# Rocketometer2148.net
KiCad netlist of a schematic drawn in EAGLE
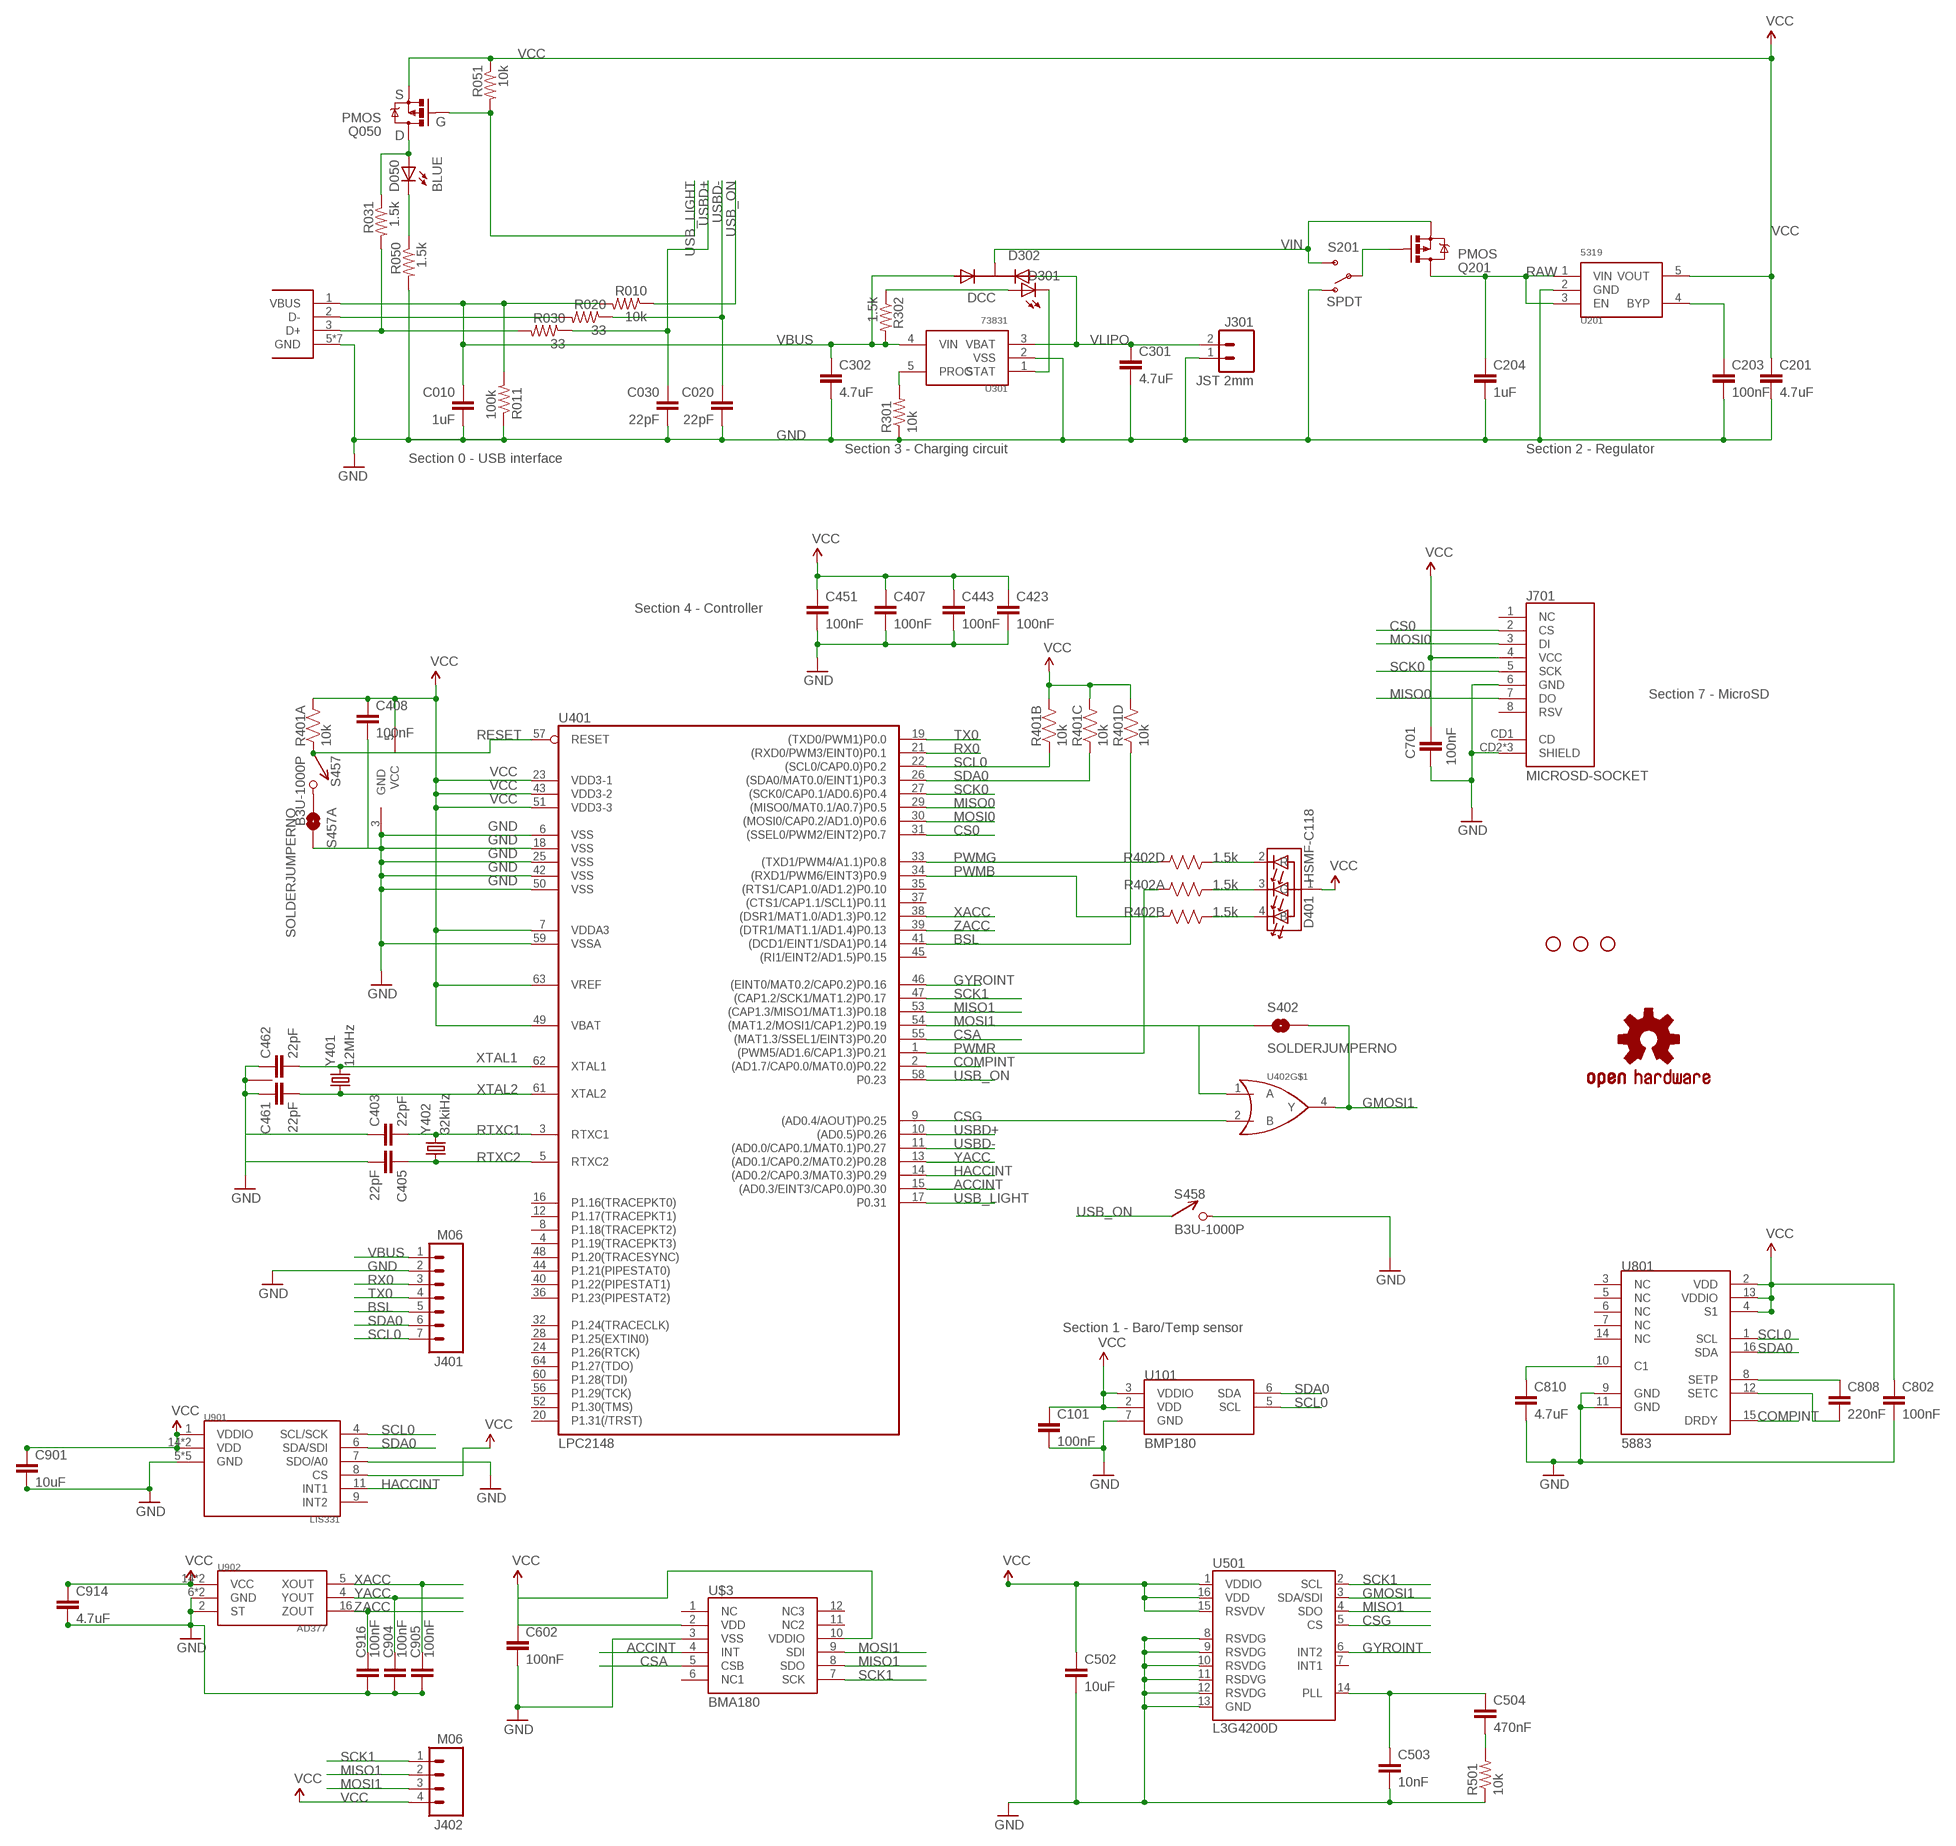
[diagram p0: schematic, sheet 1]

(export (version "E")
  (design (tool "Eeschema 10.0.6"))
  (components
    (comp (ref "C010")
      (value "1uF")
      (footprint "eagle-import:0402-CAP")
      (libsource (lib "eagle-import") (part "CAP0402-CAP"))
    )
    (comp (ref "C020")
      (value "22pF")
      (footprint "eagle-import:0402-CAP")
      (libsource (lib "eagle-import") (part "CAP0402-CAP"))
    )
    (comp (ref "C030")
      (value "22pF")
      (footprint "eagle-import:0402-CAP")
      (libsource (lib "eagle-import") (part "CAP0402-CAP"))
    )
    (comp (ref "C101")
      (value "100nF")
      (footprint "eagle-import:0402-CAP")
      (libsource (lib "eagle-import") (part "CAP0402-CAP"))
    )
    (comp (ref "C201")
      (value "4.7uF")
      (footprint "eagle-import:0402-CAP")
      (libsource (lib "eagle-import") (part "CAP0402-CAP"))
    )
    (comp (ref "C203")
      (value "100nF")
      (footprint "eagle-import:0402-CAP")
      (libsource (lib "eagle-import") (part "CAP0402-CAP"))
    )
    (comp (ref "C204")
      (value "1uF")
      (footprint "eagle-import:0402-CAP")
      (libsource (lib "eagle-import") (part "CAP0402-CAP"))
    )
    (comp (ref "C301")
      (value "4.7uF")
      (footprint "eagle-import:0402-CAP")
      (libsource (lib "eagle-import") (part "CAP0402-CAP"))
    )
    (comp (ref "C302")
      (value "4.7uF")
      (footprint "eagle-import:0402-CAP")
      (libsource (lib "eagle-import") (part "CAP0402-CAP"))
    )
    (comp (ref "C403")
      (value "22pF")
      (footprint "eagle-import:0402-CAP")
      (libsource (lib "eagle-import") (part "CAP0402-CAP"))
    )
    (comp (ref "C405")
      (value "22pF")
      (footprint "eagle-import:0402-CAP")
      (libsource (lib "eagle-import") (part "CAP0402-CAP"))
    )
    (comp (ref "C407")
      (value "100nF")
      (footprint "eagle-import:0402-CAP")
      (libsource (lib "eagle-import") (part "CAP0402-CAP"))
    )
    (comp (ref "C408")
      (value "100nF")
      (footprint "eagle-import:0402-CAP")
      (libsource (lib "eagle-import") (part "CAP0402-CAP"))
    )
    (comp (ref "C423")
      (value "100nF")
      (footprint "eagle-import:0402-CAP")
      (libsource (lib "eagle-import") (part "CAP0402-CAP"))
    )
    (comp (ref "C443")
      (value "100nF")
      (footprint "eagle-import:0402-CAP")
      (libsource (lib "eagle-import") (part "CAP0402-CAP"))
    )
    (comp (ref "C451")
      (value "100nF")
      (footprint "eagle-import:0402-CAP")
      (libsource (lib "eagle-import") (part "CAP0402-CAP"))
    )
    (comp (ref "C461")
      (value "22pF")
      (footprint "eagle-import:0402-CAP")
      (libsource (lib "eagle-import") (part "CAP0402-CAP"))
    )
    (comp (ref "C462")
      (value "22pF")
      (footprint "eagle-import:0402-CAP")
      (libsource (lib "eagle-import") (part "CAP0402-CAP"))
    )
    (comp (ref "C502")
      (value "10uF")
      (footprint "eagle-import:0603-CAP")
      (libsource (lib "eagle-import") (part "CAP0603-CAP"))
    )
    (comp (ref "C503")
      (value "10nF")
      (footprint "eagle-import:0402-CAP")
      (libsource (lib "eagle-import") (part "CAP0402-CAP"))
    )
    (comp (ref "C504")
      (value "470nF")
      (footprint "eagle-import:0402-CAP")
      (libsource (lib "eagle-import") (part "CAP0402-CAP"))
    )
    (comp (ref "C602")
      (value "100nF")
      (footprint "eagle-import:0402-CAP")
      (libsource (lib "eagle-import") (part "CAP0402-CAP"))
    )
    (comp (ref "C701")
      (value "100nF")
      (footprint "eagle-import:0402-CAP")
      (libsource (lib "eagle-import") (part "CAP0402-CAP"))
    )
    (comp (ref "C802")
      (value "100nF")
      (footprint "eagle-import:0402-CAP")
      (libsource (lib "eagle-import") (part "CAP0402-CAP"))
    )
    (comp (ref "C808")
      (value "220nF")
      (footprint "eagle-import:0402-CAP")
      (libsource (lib "eagle-import") (part "CAP0402-CAP"))
    )
    (comp (ref "C810")
      (value "4.7uF")
      (footprint "eagle-import:0402-CAP")
      (libsource (lib "eagle-import") (part "CAP0402-CAP"))
    )
    (comp (ref "C901")
      (value "10uF")
      (footprint "eagle-import:0603-CAP")
      (libsource (lib "eagle-import") (part "CAP0603-CAP"))
    )
    (comp (ref "C904")
      (value "100nF")
      (footprint "eagle-import:0402-CAP")
      (libsource (lib "eagle-import") (part "CAP0402-CAP"))
    )
    (comp (ref "C905")
      (value "100nF")
      (footprint "eagle-import:0402-CAP")
      (libsource (lib "eagle-import") (part "CAP0402-CAP"))
    )
    (comp (ref "C914")
      (value "4.7uF")
      (footprint "eagle-import:0402-CAP")
      (libsource (lib "eagle-import") (part "CAP0402-CAP"))
    )
    (comp (ref "C916")
      (value "100nF")
      (footprint "eagle-import:0402-CAP")
      (libsource (lib "eagle-import") (part "CAP0402-CAP"))
    )
    (comp (ref "D050")
      (value "BLUE")
      (footprint "eagle-import:LED-0603")
      (libsource (lib "eagle-import") (part "LED0603"))
    )
    (comp (ref "D301")
      (value "YELLOW")
      (footprint "eagle-import:LED-0603")
      (libsource (lib "eagle-import") (part "LED0603"))
    )
    (comp (ref "D302")
      (value "DCC")
      (footprint "eagle-import:SOT-23-3")
      (libsource (lib "eagle-import") (part "PMEG2005CT"))
    )
    (comp (ref "D401")
      (value "HSMF-C118")
      (footprint "eagle-import:HSMF-C118")
      (libsource (lib "eagle-import") (part "HSMF-C118"))
    )
    (comp (ref "J001")
      (value "USB_MICROB_JST")
      (footprint "eagle-import:UB-MC5BR3-SD204-4S")
      (libsource (lib "eagle-import") (part "USB_MICROB_JST"))
    )
    (comp (ref "J301")
      (value "JST 2mm")
      (footprint "eagle-import:JST-2-SMD")
      (libsource (lib "eagle-import") (part "M02-JST-2MM-SMT"))
    )
    (comp (ref "J401")
      (value "M06")
      (footprint "eagle-import:1X07")
      (libsource (lib "eagle-import") (part "M07"))
    )
    (comp (ref "J402")
      (value "M06")
      (footprint "eagle-import:1X04")
      (libsource (lib "eagle-import") (part "M04PTH"))
    )
    (comp (ref "J701")
      (value "MICROSD-SOCKET")
      (footprint "eagle-import:MICROSD-SOCKET-PP")
      (libsource (lib "eagle-import") (part "MICROSD-SOCKET"))
    )
    (comp (ref "JP1")
      (value "STAND-OFFTIGHT")
      (footprint "eagle-import:STAND-OFF-TIGHT")
      (libsource (lib "eagle-import") (part "STAND-OFFTIGHT"))
    )
    (comp (ref "JP2")
      (value "STAND-OFFTIGHT")
      (footprint "eagle-import:STAND-OFF-TIGHT")
      (libsource (lib "eagle-import") (part "STAND-OFFTIGHT"))
    )
    (comp (ref "JP3")
      (value "STAND-OFFTIGHT")
      (footprint "eagle-import:STAND-OFF-TIGHT")
      (libsource (lib "eagle-import") (part "STAND-OFFTIGHT"))
    )
    (comp (ref "Q050")
      (value "PMOS")
      (footprint "eagle-import:SOT23-3")
      (libsource (lib "eagle-import") (part "MOSFET-PCHANNELSMD"))
    )
    (comp (ref "Q201")
      (value "PMOS")
      (footprint "eagle-import:SOT23-3")
      (libsource (lib "eagle-import") (part "MOSFET-PCHANNELSMD"))
    )
    (comp (ref "R010")
      (value "10k")
      (footprint "eagle-import:0402-RES")
      (libsource (lib "eagle-import") (part "RESISTOR0402-RES"))
    )
    (comp (ref "R011")
      (value "100k")
      (footprint "eagle-import:0402-RES")
      (libsource (lib "eagle-import") (part "RESISTOR0402-RES"))
    )
    (comp (ref "R020")
      (value "33")
      (footprint "eagle-import:0402-RES")
      (libsource (lib "eagle-import") (part "RESISTOR0402-RES"))
    )
    (comp (ref "R030")
      (value "33")
      (footprint "eagle-import:0402-RES")
      (libsource (lib "eagle-import") (part "RESISTOR0402-RES"))
    )
    (comp (ref "R031")
      (value "1.5k")
      (footprint "eagle-import:0402-RES")
      (libsource (lib "eagle-import") (part "RESISTOR0402-RES"))
    )
    (comp (ref "R050")
      (value "1.5k")
      (footprint "eagle-import:0402-RES")
      (libsource (lib "eagle-import") (part "RESISTOR0402-RES"))
    )
    (comp (ref "R051")
      (value "10k")
      (footprint "eagle-import:0402-RES")
      (libsource (lib "eagle-import") (part "RESISTOR0402-RES"))
    )
    (comp (ref "R301")
      (value "10k")
      (footprint "eagle-import:0402-RES")
      (libsource (lib "eagle-import") (part "RESISTOR0402-RES"))
    )
    (comp (ref "R302")
      (value "1.5k")
      (footprint "eagle-import:0402-RES")
      (libsource (lib "eagle-import") (part "RESISTOR0402-RES"))
    )
    (comp (ref "R401")
      (value "10k")
      (footprint "eagle-import:CRA04")
      (fields (field (name "DIGIKEY") "CRA4S810KCT-ND"))
      (libsource (lib "eagle-import") (part "RP404"))
    )
    (comp (ref "R402")
      (value "1.5k")
      (footprint "eagle-import:CRA04")
      (fields (field (name "DIGIKEY") "CRA4S81.5KCT-ND"))
      (libsource (lib "eagle-import") (part "RP404"))
    )
    (comp (ref "R501")
      (value "10k")
      (footprint "eagle-import:0402-RES")
      (libsource (lib "eagle-import") (part "RESISTOR0402-RES"))
    )
    (comp (ref "S201")
      (value "SPDT")
      (footprint "eagle-import:AYZ0202")
      (libsource (lib "eagle-import") (part "SWITCH-SPSTSMD"))
    )
    (comp (ref "S402")
      (value "SOLDERJUMPERNO")
      (footprint "eagle-import:SJ_2S-NO")
      (libsource (lib "eagle-import") (part "SOLDERJUMPERNO"))
    )
    (comp (ref "S457")
      (value "B3U-1000P")
      (footprint "eagle-import:B3U-1000P")
      (libsource (lib "eagle-import") (part "B3U-1000P"))
    )
    (comp (ref "S457A")
      (value "SOLDERJUMPERNO")
      (footprint "eagle-import:SJ_2S-NO")
      (libsource (lib "eagle-import") (part "SOLDERJUMPERNO"))
    )
    (comp (ref "S458")
      (value "B3U-1000P")
      (footprint "eagle-import:B3U-1000P")
      (libsource (lib "eagle-import") (part "B3U-1000P"))
    )
    (comp (ref "U$2")
      (value "OSHW-LOGOS")
      (footprint "eagle-import:OSHW-LOGO-S")
      (libsource (lib "eagle-import") (part "OSHW-LOGOS"))
    )
    (comp (ref "U$3")
      (value "BMA180")
      (footprint "eagle-import:LGA12")
      (libsource (lib "eagle-import") (part "BMA180"))
    )
    (comp (ref "U101")
      (value "BMP180")
      (footprint "eagle-import:BMP180")
      (libsource (lib "eagle-import") (part "BMP180"))
    )
    (comp (ref "U201")
      (value "5319")
      (footprint "eagle-import:SOT-23-5")
      (libsource (lib "eagle-import") (part "MIC5319D5"))
    )
    (comp (ref "U301")
      (value "73831")
      (footprint "eagle-import:SOT-23-5")
      (libsource (lib "eagle-import") (part "MCP73831"))
    )
    (comp (ref "U401")
      (value "LPC2148")
      (footprint "eagle-import:SQFP-S-10X10-64")
      (libsource (lib "eagle-import") (part "LPC213X"))
    )
    (comp (ref "U402")
      (value "SN74LVC1G32")
      (footprint "eagle-import:SOT-23-5")
      (libsource (lib "eagle-import") (part "SN74LVC1G32"))
    )
    (comp (ref "U501")
      (value "L3G4200D")
      (footprint "eagle-import:LGA16-4X4")
      (libsource (lib "eagle-import") (part "L3G4200D"))
    )
    (comp (ref "U801")
      (value "5883")
      (footprint "eagle-import:16LPCC")
      (libsource (lib "eagle-import") (part "HMC5883LSMD"))
    )
    (comp (ref "U901")
      (value "LIS331")
      (footprint "eagle-import:LLGA16")
      (libsource (lib "eagle-import") (part "H3LIS331DL"))
    )
    (comp (ref "U902")
      (value "AD377")
      (footprint "eagle-import:ADXL377")
      (libsource (lib "eagle-import") (part "ADXL377"))
    )
    (comp (ref "Y401")
      (value "12MHz")
      (footprint "eagle-import:CRYSTAL_SMD_2MM_2_5MM")
      (libsource (lib "eagle-import") (part "CX2520"))
    )
    (comp (ref "Y402")
      (value "32kiHz")
      (footprint "eagle-import:ABS06")
      (libsource (lib "eagle-import") (part "ABS06"))
    )
  )
  (nets
    (net (code "1") (name "/ACCINT") (class "Default")
      (node (ref "U$3") (pin "4") (pinfunction "INT_4") (pintype "bidirectional"))
      (node (ref "U401") (pin "15") (pinfunction "(AD0.3/EINT3/CAP0.0)P0.30_15") (pintype "bidirectional"))
    )
    (net (code "2") (name "/BSL") (class "Default")
      (node (ref "J401") (pin "5") (pinfunction "5_5") (pintype "passive"))
      (node (ref "R401") (pin "4") (pinfunction "1_4") (pintype "passive"))
      (node (ref "U401") (pin "41") (pinfunction "(DCD1/EINT1/SDA1)P0.14_41") (pintype "bidirectional"))
    )
    (net (code "3") (name "/COMPINT") (class "Default")
      (node (ref "U401") (pin "2") (pinfunction "(AD1.7/CAP0.0/MAT0.0)P0.22_2") (pintype "bidirectional"))
      (node (ref "U801") (pin "15") (pinfunction "DRDY_15") (pintype "bidirectional"))
    )
    (net (code "4") (name "/CS0") (class "Default")
      (node (ref "J701") (pin "2") (pinfunction "CS_2") (pintype "bidirectional"))
      (node (ref "U401") (pin "31") (pinfunction "(SSEL0/PWM2/EINT2)P0.7_31") (pintype "bidirectional"))
    )
    (net (code "5") (name "/CSA") (class "Default")
      (node (ref "U$3") (pin "5") (pinfunction "CSB_5") (pintype "bidirectional"))
      (node (ref "U401") (pin "55") (pinfunction "(MAT1.3/SSEL1/EINT3)P0.20_55") (pintype "bidirectional"))
    )
    (net (code "6") (name "/CSG") (class "Default")
      (node (ref "U401") (pin "9") (pinfunction "(AD0.4/AOUT)P0.25_9") (pintype "bidirectional"))
      (node (ref "U402") (pin "2") (pinfunction "B_2") (pintype "bidirectional"))
      (node (ref "U501") (pin "5") (pinfunction "CS_5") (pintype "bidirectional"))
    )
    (net (code "7") (name "/GMOSI1") (class "Default")
      (node (ref "S402") (pin "2") (pinfunction "2_2") (pintype "passive"))
      (node (ref "U402") (pin "4") (pinfunction "Y_4") (pintype "bidirectional"))
      (node (ref "U501") (pin "3") (pinfunction "SDA/SDI_3") (pintype "bidirectional"))
    )
    (net (code "8") (name "/GYROINT") (class "Default")
      (node (ref "U401") (pin "46") (pinfunction "(EINT0/MAT0.2/CAP0.2)P0.16_46") (pintype "bidirectional"))
      (node (ref "U501") (pin "6") (pinfunction "INT2_6") (pintype "bidirectional"))
    )
    (net (code "9") (name "/HACCINT") (class "Default")
      (node (ref "U401") (pin "14") (pinfunction "(AD0.2/CAP0.3/MAT0.3)P0.29_14") (pintype "bidirectional"))
      (node (ref "U901") (pin "11") (pinfunction "INT1_11") (pintype "bidirectional"))
    )
    (net (code "10") (name "/MISO0") (class "Default")
      (node (ref "J701") (pin "7") (pinfunction "DO_7") (pintype "bidirectional"))
      (node (ref "U401") (pin "29") (pinfunction "(MISO0/MAT0.1/A0.7)P0.5_29") (pintype "bidirectional"))
    )
    (net (code "11") (name "/MISO1") (class "Default")
      (node (ref "J402") (pin "2") (pinfunction "2_2") (pintype "passive"))
      (node (ref "U$3") (pin "8") (pinfunction "SDO_8") (pintype "bidirectional"))
      (node (ref "U401") (pin "53") (pinfunction "(CAP1.3/MISO1/MAT1.3)P0.18_53") (pintype "bidirectional"))
      (node (ref "U501") (pin "4") (pinfunction "SDO_4") (pintype "bidirectional"))
    )
    (net (code "12") (name "/MOSI0") (class "Default")
      (node (ref "J701") (pin "3") (pinfunction "DI_3") (pintype "bidirectional"))
      (node (ref "U401") (pin "30") (pinfunction "(MOSI0/CAP0.2/AD1.0)P0.6_30") (pintype "bidirectional"))
    )
    (net (code "13") (name "/MOSI1") (class "Default")
      (node (ref "J402") (pin "3") (pinfunction "3_3") (pintype "passive"))
      (node (ref "S402") (pin "1") (pinfunction "1_1") (pintype "passive"))
      (node (ref "U$3") (pin "9") (pinfunction "SDI_9") (pintype "bidirectional"))
      (node (ref "U401") (pin "54") (pinfunction "(MAT1.2/MOSI1/CAP1.2)P0.19_54") (pintype "bidirectional"))
      (node (ref "U402") (pin "1") (pinfunction "A_1") (pintype "bidirectional"))
    )
    (net (code "14") (name "/PWMB") (class "Default")
      (node (ref "R402") (pin "7") (pinfunction "2_7") (pintype "passive"))
      (node (ref "U401") (pin "34") (pinfunction "(RXD1/PWM6/EINT3)P0.9_34") (pintype "bidirectional"))
    )
    (net (code "15") (name "/PWMG") (class "Default")
      (node (ref "R402") (pin "5") (pinfunction "2_5") (pintype "passive"))
      (node (ref "U401") (pin "33") (pinfunction "(TXD1/PWM4/A1.1)P0.8_33") (pintype "bidirectional"))
    )
    (net (code "16") (name "/PWMR") (class "Default")
      (node (ref "R402") (pin "8") (pinfunction "2_8") (pintype "passive"))
      (node (ref "U401") (pin "1") (pinfunction "(PWM5/AD1.6/CAP1.3)P0.21_1") (pintype "bidirectional"))
    )
    (net (code "17") (name "/RAW") (class "Default")
      (node (ref "C204") (pin "1") (pinfunction "1_1") (pintype "passive"))
      (node (ref "Q201") (pin "3") (pinfunction "D_3") (pintype "passive"))
      (node (ref "U201") (pin "1") (pinfunction "VIN_1") (pintype "bidirectional"))
      (node (ref "U201") (pin "3") (pinfunction "EN_3") (pintype "bidirectional"))
    )
    (net (code "18") (name "/RESET") (class "Default")
      (node (ref "R401") (pin "1") (pinfunction "1_1") (pintype "passive"))
      (node (ref "S457") (pin "P$1") (pinfunction "1_P$1") (pintype "bidirectional"))
      (node (ref "U401") (pin "57") (pinfunction "RESET_57") (pintype "input"))
    )
    (net (code "19") (name "/RTXC1") (class "Default")
      (node (ref "C403") (pin "2") (pinfunction "2_2") (pintype "passive"))
      (node (ref "U401") (pin "3") (pinfunction "RTXC1_3") (pintype "input"))
      (node (ref "Y402") (pin "2") (pinfunction "2_2") (pintype "passive"))
    )
    (net (code "20") (name "/RTXC2") (class "Default")
      (node (ref "C405") (pin "1") (pinfunction "1_1") (pintype "passive"))
      (node (ref "U401") (pin "5") (pinfunction "RTXC2_5") (pintype "output"))
      (node (ref "Y402") (pin "1") (pinfunction "1_1") (pintype "passive"))
    )
    (net (code "21") (name "/RX0") (class "Default")
      (node (ref "J401") (pin "3") (pinfunction "3_3") (pintype "passive"))
      (node (ref "U401") (pin "21") (pinfunction "(RXD0/PWM3/EINT0)P0.1_21") (pintype "bidirectional"))
    )
    (net (code "22") (name "/SCK0") (class "Default")
      (node (ref "J701") (pin "5") (pinfunction "SCK_5") (pintype "bidirectional"))
      (node (ref "U401") (pin "27") (pinfunction "(SCK0/CAP0.1/AD0.6)P0.4_27") (pintype "bidirectional"))
    )
    (net (code "23") (name "/SCK1") (class "Default")
      (node (ref "J402") (pin "1") (pinfunction "1_1") (pintype "passive"))
      (node (ref "U$3") (pin "7") (pinfunction "SCK_7") (pintype "bidirectional"))
      (node (ref "U401") (pin "47") (pinfunction "(CAP1.2/SCK1/MAT1.2)P0.17_47") (pintype "bidirectional"))
      (node (ref "U501") (pin "2") (pinfunction "SCL_2") (pintype "bidirectional"))
    )
    (net (code "24") (name "/SCL0") (class "Default")
      (node (ref "J401") (pin "7") (pinfunction "7_7") (pintype "passive"))
      (node (ref "R401") (pin "2") (pinfunction "1_2") (pintype "passive"))
      (node (ref "U101") (pin "5") (pinfunction "SCL_5") (pintype "input"))
      (node (ref "U401") (pin "22") (pinfunction "(SCL0/CAP0.0)P0.2_22") (pintype "bidirectional"))
      (node (ref "U801") (pin "1") (pinfunction "SCL_1") (pintype "bidirectional"))
      (node (ref "U901") (pin "4") (pinfunction "SCL/SCK_4") (pintype "bidirectional"))
    )
    (net (code "25") (name "/SDA0") (class "Default")
      (node (ref "J401") (pin "6") (pinfunction "6_6") (pintype "passive"))
      (node (ref "R401") (pin "3") (pinfunction "1_3") (pintype "passive"))
      (node (ref "U101") (pin "6") (pinfunction "SDA_6") (pintype "bidirectional"))
      (node (ref "U401") (pin "26") (pinfunction "(SDA0/MAT0.0/EINT1)P0.3_26") (pintype "bidirectional"))
      (node (ref "U801") (pin "16") (pinfunction "SDA_16") (pintype "bidirectional"))
      (node (ref "U901") (pin "6") (pinfunction "SDA/SDI_6") (pintype "bidirectional"))
    )
    (net (code "26") (name "/TX0") (class "Default")
      (node (ref "J401") (pin "4") (pinfunction "4_4") (pintype "passive"))
      (node (ref "U401") (pin "19") (pinfunction "(TXD0/PWM1)P0.0_19") (pintype "bidirectional"))
    )
    (net (code "27") (name "/USBD+") (class "Default")
      (node (ref "C030") (pin "1") (pinfunction "1_1") (pintype "passive"))
      (node (ref "R030") (pin "1") (pinfunction "1_1") (pintype "passive"))
      (node (ref "U401") (pin "10") (pinfunction "(AD0.5)P0.26_10") (pintype "bidirectional"))
    )
    (net (code "28") (name "/USBD-") (class "Default")
      (node (ref "C020") (pin "1") (pinfunction "1_1") (pintype "passive"))
      (node (ref "R020") (pin "1") (pinfunction "1_1") (pintype "passive"))
      (node (ref "U401") (pin "11") (pinfunction "(AD0.0/CAP0.1/MAT0.1)P0.27_11") (pintype "bidirectional"))
    )
    (net (code "29") (name "/USB_LIGHT") (class "Default")
      (node (ref "Q050") (pin "1") (pinfunction "G_1") (pintype "passive"))
      (node (ref "R051") (pin "2") (pinfunction "2_2") (pintype "passive"))
      (node (ref "U401") (pin "17") (pinfunction "P0.31_17") (pintype "output"))
    )
    (net (code "30") (name "/USB_ON") (class "Default")
      (node (ref "R010") (pin "1") (pinfunction "1_1") (pintype "passive"))
      (node (ref "S458") (pin "P$1") (pinfunction "1_P$1") (pintype "bidirectional"))
      (node (ref "U401") (pin "58") (pinfunction "P0.23_58") (pintype "bidirectional"))
    )
    (net (code "31") (name "/VBUS") (class "Default")
      (node (ref "C010") (pin "1") (pinfunction "1_1") (pintype "passive"))
      (node (ref "C302") (pin "1") (pinfunction "1_1") (pintype "passive"))
      (node (ref "D302") (pin "1") (pinfunction "A1_1") (pintype "passive"))
      (node (ref "J001") (pin "1") (pinfunction "VBUS_1") (pintype "bidirectional"))
      (node (ref "J401") (pin "1") (pinfunction "1_1") (pintype "passive"))
      (node (ref "R010") (pin "2") (pinfunction "2_2") (pintype "passive"))
      (node (ref "R011") (pin "2") (pinfunction "2_2") (pintype "passive"))
      (node (ref "R302") (pin "2") (pinfunction "2_2") (pintype "passive"))
      (node (ref "U301") (pin "4") (pinfunction "VIN_4") (pintype "bidirectional"))
    )
    (net (code "32") (name "/VIN") (class "Default")
      (node (ref "D302") (pin "3") (pinfunction "K_3") (pintype "passive"))
      (node (ref "Q201") (pin "2") (pinfunction "S_2") (pintype "passive"))
      (node (ref "S201") (pin "3") (pinfunction "S_3") (pintype "passive"))
    )
    (net (code "33") (name "/VLIPO") (class "Default")
      (node (ref "C301") (pin "1") (pinfunction "1_1") (pintype "passive"))
      (node (ref "D302") (pin "2") (pinfunction "A2_2") (pintype "passive"))
      (node (ref "J301") (pin "2") (pinfunction "2_2") (pintype "passive"))
      (node (ref "U301") (pin "3") (pinfunction "VBAT_3") (pintype "bidirectional"))
    )
    (net (code "34") (name "/XACC") (class "Default")
      (node (ref "C905") (pin "1") (pinfunction "1_1") (pintype "passive"))
      (node (ref "U401") (pin "38") (pinfunction "(DSR1/MAT1.0/AD1.3)P0.12_38") (pintype "bidirectional"))
      (node (ref "U902") (pin "5") (pinfunction "XOUT_5") (pintype "bidirectional"))
    )
    (net (code "35") (name "/XTAL1") (class "Default")
      (node (ref "C462") (pin "2") (pinfunction "2_2") (pintype "passive"))
      (node (ref "U401") (pin "62") (pinfunction "XTAL1_62") (pintype "input"))
      (node (ref "Y401") (pin "3") (pinfunction "2_3") (pintype "passive"))
    )
    (net (code "36") (name "/XTAL2") (class "Default")
      (node (ref "C461") (pin "2") (pinfunction "2_2") (pintype "passive"))
      (node (ref "U401") (pin "61") (pinfunction "XTAL2_61") (pintype "output"))
      (node (ref "Y401") (pin "1") (pinfunction "1_1") (pintype "passive"))
    )
    (net (code "37") (name "/YACC") (class "Default")
      (node (ref "C904") (pin "1") (pinfunction "1_1") (pintype "passive"))
      (node (ref "U401") (pin "13") (pinfunction "(AD0.1/CAP0.2/MAT0.2)P0.28_13") (pintype "bidirectional"))
      (node (ref "U902") (pin "4") (pinfunction "YOUT_4") (pintype "bidirectional"))
    )
    (net (code "38") (name "/ZACC") (class "Default")
      (node (ref "C916") (pin "1") (pinfunction "1_1") (pintype "passive"))
      (node (ref "U401") (pin "39") (pinfunction "(DTR1/MAT1.1/AD1.4)P0.13_39") (pintype "bidirectional"))
      (node (ref "U902") (pin "16") (pinfunction "ZOUT_16") (pintype "bidirectional"))
    )
    (net (code "39") (name "GND") (class "Default")
      (node (ref "C010") (pin "2") (pinfunction "2_2") (pintype "passive"))
      (node (ref "C020") (pin "2") (pinfunction "2_2") (pintype "passive"))
      (node (ref "C030") (pin "2") (pinfunction "2_2") (pintype "passive"))
      (node (ref "C101") (pin "2") (pinfunction "2_2") (pintype "passive"))
      (node (ref "C201") (pin "2") (pinfunction "2_2") (pintype "passive"))
      (node (ref "C203") (pin "2") (pinfunction "2_2") (pintype "passive"))
      (node (ref "C204") (pin "2") (pinfunction "2_2") (pintype "passive"))
      (node (ref "C301") (pin "2") (pinfunction "2_2") (pintype "passive"))
      (node (ref "C302") (pin "2") (pinfunction "2_2") (pintype "passive"))
      (node (ref "C403") (pin "1") (pinfunction "1_1") (pintype "passive"))
      (node (ref "C405") (pin "2") (pinfunction "2_2") (pintype "passive"))
      (node (ref "C407") (pin "2") (pinfunction "2_2") (pintype "passive"))
      (node (ref "C408") (pin "2") (pinfunction "2_2") (pintype "passive"))
      (node (ref "C423") (pin "2") (pinfunction "2_2") (pintype "passive"))
      (node (ref "C443") (pin "2") (pinfunction "2_2") (pintype "passive"))
      (node (ref "C451") (pin "2") (pinfunction "2_2") (pintype "passive"))
      (node (ref "C461") (pin "1") (pinfunction "1_1") (pintype "passive"))
      (node (ref "C462") (pin "1") (pinfunction "1_1") (pintype "passive"))
      (node (ref "C502") (pin "2") (pinfunction "2_2") (pintype "passive"))
      (node (ref "C503") (pin "2") (pinfunction "2_2") (pintype "passive"))
      (node (ref "C602") (pin "2") (pinfunction "2_2") (pintype "passive"))
      (node (ref "C701") (pin "2") (pinfunction "2_2") (pintype "passive"))
      (node (ref "C802") (pin "2") (pinfunction "2_2") (pintype "passive"))
      (node (ref "C810") (pin "2") (pinfunction "2_2") (pintype "passive"))
      (node (ref "C901") (pin "2") (pinfunction "2_2") (pintype "passive"))
      (node (ref "C904") (pin "2") (pinfunction "2_2") (pintype "passive"))
      (node (ref "C905") (pin "2") (pinfunction "2_2") (pintype "passive"))
      (node (ref "C914") (pin "2") (pinfunction "2_2") (pintype "passive"))
      (node (ref "C916") (pin "2") (pinfunction "2_2") (pintype "passive"))
      (node (ref "J001") (pin "5") (pinfunction "GND_5") (pintype "bidirectional"))
      (node (ref "J001") (pin "P$10") (pinfunction "GND_P$10") (pintype "bidirectional"))
      (node (ref "J001") (pin "P$11") (pinfunction "GND_P$11") (pintype "bidirectional"))
      (node (ref "J001") (pin "P$6") (pinfunction "GND_P$6") (pintype "bidirectional"))
      (node (ref "J001") (pin "P$7") (pinfunction "GND_P$7") (pintype "bidirectional"))
      (node (ref "J001") (pin "P$8") (pinfunction "GND_P$8") (pintype "bidirectional"))
      (node (ref "J001") (pin "P$9") (pinfunction "GND_P$9") (pintype "bidirectional"))
      (node (ref "J301") (pin "1") (pinfunction "1_1") (pintype "passive"))
      (node (ref "J401") (pin "2") (pinfunction "2_2") (pintype "passive"))
      (node (ref "J701") (pin "6") (pinfunction "GND_6") (pintype "bidirectional"))
      (node (ref "J701") (pin "CD2") (pinfunction "SHIELD_CD2") (pintype "bidirectional"))
      (node (ref "J701") (pin "GND1") (pinfunction "SHIELD_GND1") (pintype "bidirectional"))
      (node (ref "J701") (pin "GND3") (pinfunction "SHIELD_GND3") (pintype "bidirectional"))
      (node (ref "R011") (pin "1") (pinfunction "1_1") (pintype "passive"))
      (node (ref "R050") (pin "2") (pinfunction "2_2") (pintype "passive"))
      (node (ref "R301") (pin "1") (pinfunction "1_1") (pintype "passive"))
      (node (ref "R501") (pin "1") (pinfunction "1_1") (pintype "passive"))
      (node (ref "S201") (pin "1") (pinfunction "O_1") (pintype "passive"))
      (node (ref "S457A") (pin "2") (pinfunction "2_2") (pintype "passive"))
      (node (ref "S458") (pin "P$2") (pinfunction "2_P$2") (pintype "bidirectional"))
      (node (ref "U$3") (pin "3") (pinfunction "VSS_3") (pintype "bidirectional"))
      (node (ref "U101") (pin "7") (pinfunction "GND_7") (pintype "power_in"))
      (node (ref "U201") (pin "2") (pinfunction "GND_2") (pintype "bidirectional"))
      (node (ref "U301") (pin "2") (pinfunction "VSS_2") (pintype "bidirectional"))
      (node (ref "U401") (pin "18") (pinfunction "VSS_18") (pintype "power_in"))
      (node (ref "U401") (pin "25") (pinfunction "VSS_25") (pintype "power_in"))
      (node (ref "U401") (pin "42") (pinfunction "VSS_42") (pintype "power_in"))
      (node (ref "U401") (pin "50") (pinfunction "VSS_50") (pintype "power_in"))
      (node (ref "U401") (pin "59") (pinfunction "VSSA_59") (pintype "power_in"))
      (node (ref "U401") (pin "6") (pinfunction "VSS_6") (pintype "power_in"))
      (node (ref "U402") (pin "3") (pinfunction "GND_3") (pintype "bidirectional"))
      (node (ref "U501") (pin "10") (pinfunction "RSVDG_10") (pintype "bidirectional"))
      (node (ref "U501") (pin "11") (pinfunction "RSDVG_11") (pintype "bidirectional"))
      (node (ref "U501") (pin "12") (pinfunction "RSVDG_12") (pintype "bidirectional"))
      (node (ref "U501") (pin "13") (pinfunction "GND_13") (pintype "bidirectional"))
      (node (ref "U501") (pin "8") (pinfunction "RSVDG_8") (pintype "bidirectional"))
      (node (ref "U501") (pin "9") (pinfunction "RSVDG_9") (pintype "bidirectional"))
      (node (ref "U801") (pin "11") (pinfunction "GND_11") (pintype "bidirectional"))
      (node (ref "U801") (pin "9") (pinfunction "GND_9") (pintype "bidirectional"))
      (node (ref "U901") (pin "10") (pinfunction "GND_10") (pintype "bidirectional"))
      (node (ref "U901") (pin "12") (pinfunction "GND_12") (pintype "bidirectional"))
      (node (ref "U901") (pin "13") (pinfunction "GND_13") (pintype "bidirectional"))
      (node (ref "U901") (pin "16") (pinfunction "GND_16") (pintype "bidirectional"))
      (node (ref "U901") (pin "5") (pinfunction "GND_5") (pintype "bidirectional"))
      (node (ref "U901") (pin "7") (pinfunction "SDO/A0_7") (pintype "bidirectional"))
      (node (ref "U902") (pin "2") (pinfunction "ST_2") (pintype "bidirectional"))
      (node (ref "U902") (pin "6") (pinfunction "GND_6") (pintype "bidirectional"))
      (node (ref "U902") (pin "7") (pinfunction "GND_7") (pintype "bidirectional"))
      (node (ref "Y401") (pin "2") (pinfunction "1_2") (pintype "bidirectional"))
      (node (ref "Y401") (pin "4") (pinfunction "1_4") (pintype "bidirectional"))
    )
    (net (code "40") (name "Net-(C504-Pad2)") (class "Default")
      (node (ref "C504") (pin "2") (pinfunction "2_2") (pintype "passive"))
      (node (ref "R501") (pin "2") (pinfunction "2_2") (pintype "passive"))
    )
    (net (code "41") (name "Net-(D050-PadC)") (class "Default")
      (node (ref "D050") (pin "C") (pinfunction "C_C") (pintype "passive"))
      (node (ref "R050") (pin "1") (pinfunction "1_1") (pintype "passive"))
    )
    (net (code "42") (name "Net-(D301-PadA)") (class "Default")
      (node (ref "D301") (pin "A") (pinfunction "A_A") (pintype "passive"))
      (node (ref "R302") (pin "1") (pinfunction "1_1") (pintype "passive"))
    )
    (net (code "43") (name "Net-(D401-B)") (class "Default")
      (node (ref "D401") (pin "4") (pinfunction "B_4") (pintype "passive"))
      (node (ref "R402") (pin "2") (pinfunction "1_2") (pintype "passive"))
    )
    (net (code "44") (name "Net-(D401-G)") (class "Default")
      (node (ref "D401") (pin "3") (pinfunction "G_3") (pintype "passive"))
      (node (ref "R402") (pin "1") (pinfunction "1_1") (pintype "passive"))
    )
    (net (code "45") (name "Net-(D401-R)") (class "Default")
      (node (ref "D401") (pin "2") (pinfunction "R_2") (pintype "passive"))
      (node (ref "R402") (pin "4") (pinfunction "1_4") (pintype "passive"))
    )
    (net (code "46") (name "Net-(J001-D+)") (class "Default")
      (node (ref "J001") (pin "3") (pinfunction "D+_3") (pintype "bidirectional"))
      (node (ref "R030") (pin "2") (pinfunction "2_2") (pintype "passive"))
      (node (ref "R031") (pin "2") (pinfunction "2_2") (pintype "passive"))
    )
    (net (code "47") (name "Net-(J001-D-)") (class "Default")
      (node (ref "J001") (pin "2") (pinfunction "D-_2") (pintype "bidirectional"))
      (node (ref "R020") (pin "2") (pinfunction "2_2") (pintype "passive"))
    )
    (net (code "48") (name "Net-(Q050-D)") (class "Default")
      (node (ref "D050") (pin "A") (pinfunction "A_A") (pintype "passive"))
      (node (ref "Q050") (pin "3") (pinfunction "D_3") (pintype "passive"))
      (node (ref "R031") (pin "1") (pinfunction "1_1") (pintype "passive"))
    )
    (net (code "49") (name "Net-(Q201-G)") (class "Default")
      (node (ref "Q201") (pin "1") (pinfunction "G_1") (pintype "passive"))
      (node (ref "S201") (pin "2") (pinfunction "P_2") (pintype "passive"))
    )
    (net (code "50") (name "Net-(S457-2)") (class "Default")
      (node (ref "S457") (pin "P$2") (pinfunction "2_P$2") (pintype "bidirectional"))
      (node (ref "S457A") (pin "1") (pinfunction "1_1") (pintype "passive"))
    )
    (net (code "51") (name "Net-(U201-BYP)") (class "Default")
      (node (ref "C203") (pin "1") (pinfunction "1_1") (pintype "passive"))
      (node (ref "U201") (pin "4") (pinfunction "BYP_4") (pintype "bidirectional"))
    )
    (net (code "52") (name "Net-(U301-PROG)") (class "Default")
      (node (ref "R301") (pin "2") (pinfunction "2_2") (pintype "passive"))
      (node (ref "U301") (pin "5") (pinfunction "PROG_5") (pintype "bidirectional"))
    )
    (net (code "53") (name "Net-(U301-STAT)") (class "Default")
      (node (ref "D301") (pin "C") (pinfunction "C_C") (pintype "passive"))
      (node (ref "U301") (pin "1") (pinfunction "STAT_1") (pintype "bidirectional"))
    )
    (net (code "54") (name "Net-(U501-PLL)") (class "Default")
      (node (ref "C503") (pin "1") (pinfunction "1_1") (pintype "passive"))
      (node (ref "C504") (pin "1") (pinfunction "1_1") (pintype "passive"))
      (node (ref "U501") (pin "14") (pinfunction "PLL_14") (pintype "bidirectional"))
    )
    (net (code "55") (name "Net-(U801-C1)") (class "Default")
      (node (ref "C810") (pin "1") (pinfunction "1_1") (pintype "passive"))
      (node (ref "U801") (pin "10") (pinfunction "C1_10") (pintype "bidirectional"))
    )
    (net (code "56") (name "Net-(U801-SETC)") (class "Default")
      (node (ref "C808") (pin "2") (pinfunction "2_2") (pintype "passive"))
      (node (ref "U801") (pin "12") (pinfunction "SETC_12") (pintype "bidirectional"))
    )
    (net (code "57") (name "Net-(U801-SETP)") (class "Default")
      (node (ref "C808") (pin "1") (pinfunction "1_1") (pintype "passive"))
      (node (ref "U801") (pin "8") (pinfunction "SETP_8") (pintype "bidirectional"))
    )
    (net (code "58") (name "VCC") (class "Default")
      (node (ref "C101") (pin "1") (pinfunction "1_1") (pintype "passive"))
      (node (ref "C201") (pin "1") (pinfunction "1_1") (pintype "passive"))
      (node (ref "C407") (pin "1") (pinfunction "1_1") (pintype "passive"))
      (node (ref "C408") (pin "1") (pinfunction "1_1") (pintype "passive"))
      (node (ref "C423") (pin "1") (pinfunction "1_1") (pintype "passive"))
      (node (ref "C443") (pin "1") (pinfunction "1_1") (pintype "passive"))
      (node (ref "C451") (pin "1") (pinfunction "1_1") (pintype "passive"))
      (node (ref "C502") (pin "1") (pinfunction "1_1") (pintype "passive"))
      (node (ref "C602") (pin "1") (pinfunction "1_1") (pintype "passive"))
      (node (ref "C701") (pin "1") (pinfunction "1_1") (pintype "passive"))
      (node (ref "C802") (pin "1") (pinfunction "1_1") (pintype "passive"))
      (node (ref "C901") (pin "1") (pinfunction "1_1") (pintype "passive"))
      (node (ref "C914") (pin "1") (pinfunction "1_1") (pintype "passive"))
      (node (ref "D401") (pin "1") (pinfunction "A_1") (pintype "passive"))
      (node (ref "J402") (pin "4") (pinfunction "4_4") (pintype "passive"))
      (node (ref "J701") (pin "4") (pinfunction "VCC_4") (pintype "bidirectional"))
      (node (ref "Q050") (pin "2") (pinfunction "S_2") (pintype "passive"))
      (node (ref "R051") (pin "1") (pinfunction "1_1") (pintype "passive"))
      (node (ref "R401") (pin "5") (pinfunction "2_5") (pintype "passive"))
      (node (ref "R401") (pin "6") (pinfunction "2_6") (pintype "passive"))
      (node (ref "R401") (pin "7") (pinfunction "2_7") (pintype "passive"))
      (node (ref "R401") (pin "8") (pinfunction "2_8") (pintype "passive"))
      (node (ref "U$3") (pin "10") (pinfunction "VDDIO_10") (pintype "bidirectional"))
      (node (ref "U$3") (pin "2") (pinfunction "VDD_2") (pintype "bidirectional"))
      (node (ref "U101") (pin "2") (pinfunction "VDD_2") (pintype "power_in"))
      (node (ref "U101") (pin "3") (pinfunction "VDDIO_3") (pintype "power_in"))
      (node (ref "U201") (pin "5") (pinfunction "VOUT_5") (pintype "bidirectional"))
      (node (ref "U401") (pin "23") (pinfunction "VDD3-1_23") (pintype "power_in"))
      (node (ref "U401") (pin "43") (pinfunction "VDD3-2_43") (pintype "power_in"))
      (node (ref "U401") (pin "49") (pinfunction "VBAT_49") (pintype "power_in"))
      (node (ref "U401") (pin "51") (pinfunction "VDD3-3_51") (pintype "power_in"))
      (node (ref "U401") (pin "63") (pinfunction "VREF_63") (pintype "input"))
      (node (ref "U401") (pin "7") (pinfunction "VDDA3_7") (pintype "power_in"))
      (node (ref "U402") (pin "5") (pinfunction "VCC_5") (pintype "bidirectional"))
      (node (ref "U501") (pin "1") (pinfunction "VDDIO_1") (pintype "bidirectional"))
      (node (ref "U501") (pin "15") (pinfunction "RSVDV_15") (pintype "bidirectional"))
      (node (ref "U501") (pin "16") (pinfunction "VDD_16") (pintype "bidirectional"))
      (node (ref "U801") (pin "13") (pinfunction "VDDIO_13") (pintype "bidirectional"))
      (node (ref "U801") (pin "2") (pinfunction "VDD_2") (pintype "bidirectional"))
      (node (ref "U801") (pin "4") (pinfunction "S1_4") (pintype "bidirectional"))
      (node (ref "U901") (pin "1") (pinfunction "VDDIO_1") (pintype "bidirectional"))
      (node (ref "U901") (pin "14") (pinfunction "VDD_14") (pintype "bidirectional"))
      (node (ref "U901") (pin "15") (pinfunction "VDD_15") (pintype "bidirectional"))
      (node (ref "U901") (pin "8") (pinfunction "CS_8") (pintype "bidirectional"))
      (node (ref "U902") (pin "14") (pinfunction "VCC_14") (pintype "bidirectional"))
      (node (ref "U902") (pin "15") (pinfunction "VCC_15") (pintype "bidirectional"))
    )
    (net (code "59") (name "unconnected-(J701-CD-PadCD1)") (class "Default")
      (node (ref "J701") (pin "CD1") (pinfunction "CD_CD1") (pintype "bidirectional"))
    )
    (net (code "60") (name "unconnected-(J701-NC-Pad1)") (class "Default")
      (node (ref "J701") (pin "1") (pinfunction "NC_1") (pintype "bidirectional"))
    )
    (net (code "61") (name "unconnected-(J701-RSV-Pad8)") (class "Default")
      (node (ref "J701") (pin "8") (pinfunction "RSV_8") (pintype "bidirectional"))
    )
    (net (code "62") (name "unconnected-(U$3-NC-Pad1)") (class "Default")
      (node (ref "U$3") (pin "1") (pinfunction "NC_1") (pintype "bidirectional"))
    )
    (net (code "63") (name "unconnected-(U$3-NC1-Pad6)") (class "Default")
      (node (ref "U$3") (pin "6") (pinfunction "NC1_6") (pintype "bidirectional"))
    )
    (net (code "64") (name "unconnected-(U$3-NC2-Pad11)") (class "Default")
      (node (ref "U$3") (pin "11") (pinfunction "NC2_11") (pintype "bidirectional"))
    )
    (net (code "65") (name "unconnected-(U$3-NC3-Pad12)") (class "Default")
      (node (ref "U$3") (pin "12") (pinfunction "NC3_12") (pintype "bidirectional"))
    )
    (net (code "66") (name "unconnected-(U401-(CTS1{slash}CAP1.1{slash}SCL1)P0.11-Pad37)") (class "Default")
      (node (ref "U401") (pin "37") (pinfunction "(CTS1/CAP1.1/SCL1)P0.11_37") (pintype "bidirectional"))
    )
    (net (code "67") (name "unconnected-(U401-(RI1{slash}EINT2{slash}AD1.5)P0.15-Pad45)") (class "Default")
      (node (ref "U401") (pin "45") (pinfunction "(RI1/EINT2/AD1.5)P0.15_45") (pintype "bidirectional"))
    )
    (net (code "68") (name "unconnected-(U401-(RTS1{slash}CAP1.0{slash}AD1.2)P0.10-Pad35)") (class "Default")
      (node (ref "U401") (pin "35") (pinfunction "(RTS1/CAP1.0/AD1.2)P0.10_35") (pintype "bidirectional"))
    )
    (net (code "69") (name "unconnected-(U401-P1.16(TRACEPKT0)-Pad16)") (class "Default")
      (node (ref "U401") (pin "16") (pinfunction "P1.16(TRACEPKT0)_16") (pintype "bidirectional"))
    )
    (net (code "70") (name "unconnected-(U401-P1.17(TRACEPKT1)-Pad12)") (class "Default")
      (node (ref "U401") (pin "12") (pinfunction "P1.17(TRACEPKT1)_12") (pintype "bidirectional"))
    )
    (net (code "71") (name "unconnected-(U401-P1.18(TRACEPKT2)-Pad8)") (class "Default")
      (node (ref "U401") (pin "8") (pinfunction "P1.18(TRACEPKT2)_8") (pintype "bidirectional"))
    )
    (net (code "72") (name "unconnected-(U401-P1.19(TRACEPKT3)-Pad4)") (class "Default")
      (node (ref "U401") (pin "4") (pinfunction "P1.19(TRACEPKT3)_4") (pintype "bidirectional"))
    )
    (net (code "73") (name "unconnected-(U401-P1.20(TRACESYNC)-Pad48)") (class "Default")
      (node (ref "U401") (pin "48") (pinfunction "P1.20(TRACESYNC)_48") (pintype "bidirectional"))
    )
    (net (code "74") (name "unconnected-(U401-P1.21(PIPESTAT0)-Pad44)") (class "Default")
      (node (ref "U401") (pin "44") (pinfunction "P1.21(PIPESTAT0)_44") (pintype "bidirectional"))
    )
    (net (code "75") (name "unconnected-(U401-P1.22(PIPESTAT1)-Pad40)") (class "Default")
      (node (ref "U401") (pin "40") (pinfunction "P1.22(PIPESTAT1)_40") (pintype "bidirectional"))
    )
    (net (code "76") (name "unconnected-(U401-P1.23(PIPESTAT2)-Pad36)") (class "Default")
      (node (ref "U401") (pin "36") (pinfunction "P1.23(PIPESTAT2)_36") (pintype "bidirectional"))
    )
    (net (code "77") (name "unconnected-(U401-P1.24(TRACECLK)-Pad32)") (class "Default")
      (node (ref "U401") (pin "32") (pinfunction "P1.24(TRACECLK)_32") (pintype "bidirectional"))
    )
    (net (code "78") (name "unconnected-(U401-P1.25(EXTIN0)-Pad28)") (class "Default")
      (node (ref "U401") (pin "28") (pinfunction "P1.25(EXTIN0)_28") (pintype "bidirectional"))
    )
    (net (code "79") (name "unconnected-(U401-P1.26(RTCK)-Pad24)") (class "Default")
      (node (ref "U401") (pin "24") (pinfunction "P1.26(RTCK)_24") (pintype "bidirectional"))
    )
    (net (code "80") (name "unconnected-(U401-P1.27(TDO)-Pad64)") (class "Default")
      (node (ref "U401") (pin "64") (pinfunction "P1.27(TDO)_64") (pintype "bidirectional"))
    )
    (net (code "81") (name "unconnected-(U401-P1.28(TDI)-Pad60)") (class "Default")
      (node (ref "U401") (pin "60") (pinfunction "P1.28(TDI)_60") (pintype "bidirectional"))
    )
    (net (code "82") (name "unconnected-(U401-P1.29(TCK)-Pad56)") (class "Default")
      (node (ref "U401") (pin "56") (pinfunction "P1.29(TCK)_56") (pintype "bidirectional"))
    )
    (net (code "83") (name "unconnected-(U401-P1.30(TMS)-Pad52)") (class "Default")
      (node (ref "U401") (pin "52") (pinfunction "P1.30(TMS)_52") (pintype "bidirectional"))
    )
    (net (code "84") (name "unconnected-(U401-P1.31({slash}TRST)-Pad20)") (class "Default")
      (node (ref "U401") (pin "20") (pinfunction "P1.31(/TRST)_20") (pintype "bidirectional"))
    )
    (net (code "85") (name "unconnected-(U501-INT1-Pad7)") (class "Default")
      (node (ref "U501") (pin "7") (pinfunction "INT1_7") (pintype "bidirectional"))
    )
    (net (code "86") (name "unconnected-(U801-NC-Pad3)") (class "Default")
      (node (ref "U801") (pin "3") (pinfunction "NC_3") (pintype "bidirectional"))
    )
    (net (code "87") (name "unconnected-(U801-NC-Pad5)") (class "Default")
      (node (ref "U801") (pin "5") (pinfunction "NC_5") (pintype "bidirectional"))
    )
    (net (code "88") (name "unconnected-(U801-NC-Pad6)") (class "Default")
      (node (ref "U801") (pin "6") (pinfunction "NC_6") (pintype "bidirectional"))
    )
    (net (code "89") (name "unconnected-(U801-NC-Pad7)") (class "Default")
      (node (ref "U801") (pin "7") (pinfunction "NC_7") (pintype "bidirectional"))
    )
    (net (code "90") (name "unconnected-(U801-NC-Pad14)") (class "Default")
      (node (ref "U801") (pin "14") (pinfunction "NC_14") (pintype "bidirectional"))
    )
    (net (code "91") (name "unconnected-(U901-INT2-Pad9)") (class "Default")
      (node (ref "U901") (pin "9") (pinfunction "INT2_9") (pintype "bidirectional"))
    )
  )
)
